# Arduino_Dots_Matrix.net
KiCad netlist of a schematic drawn in EAGLE
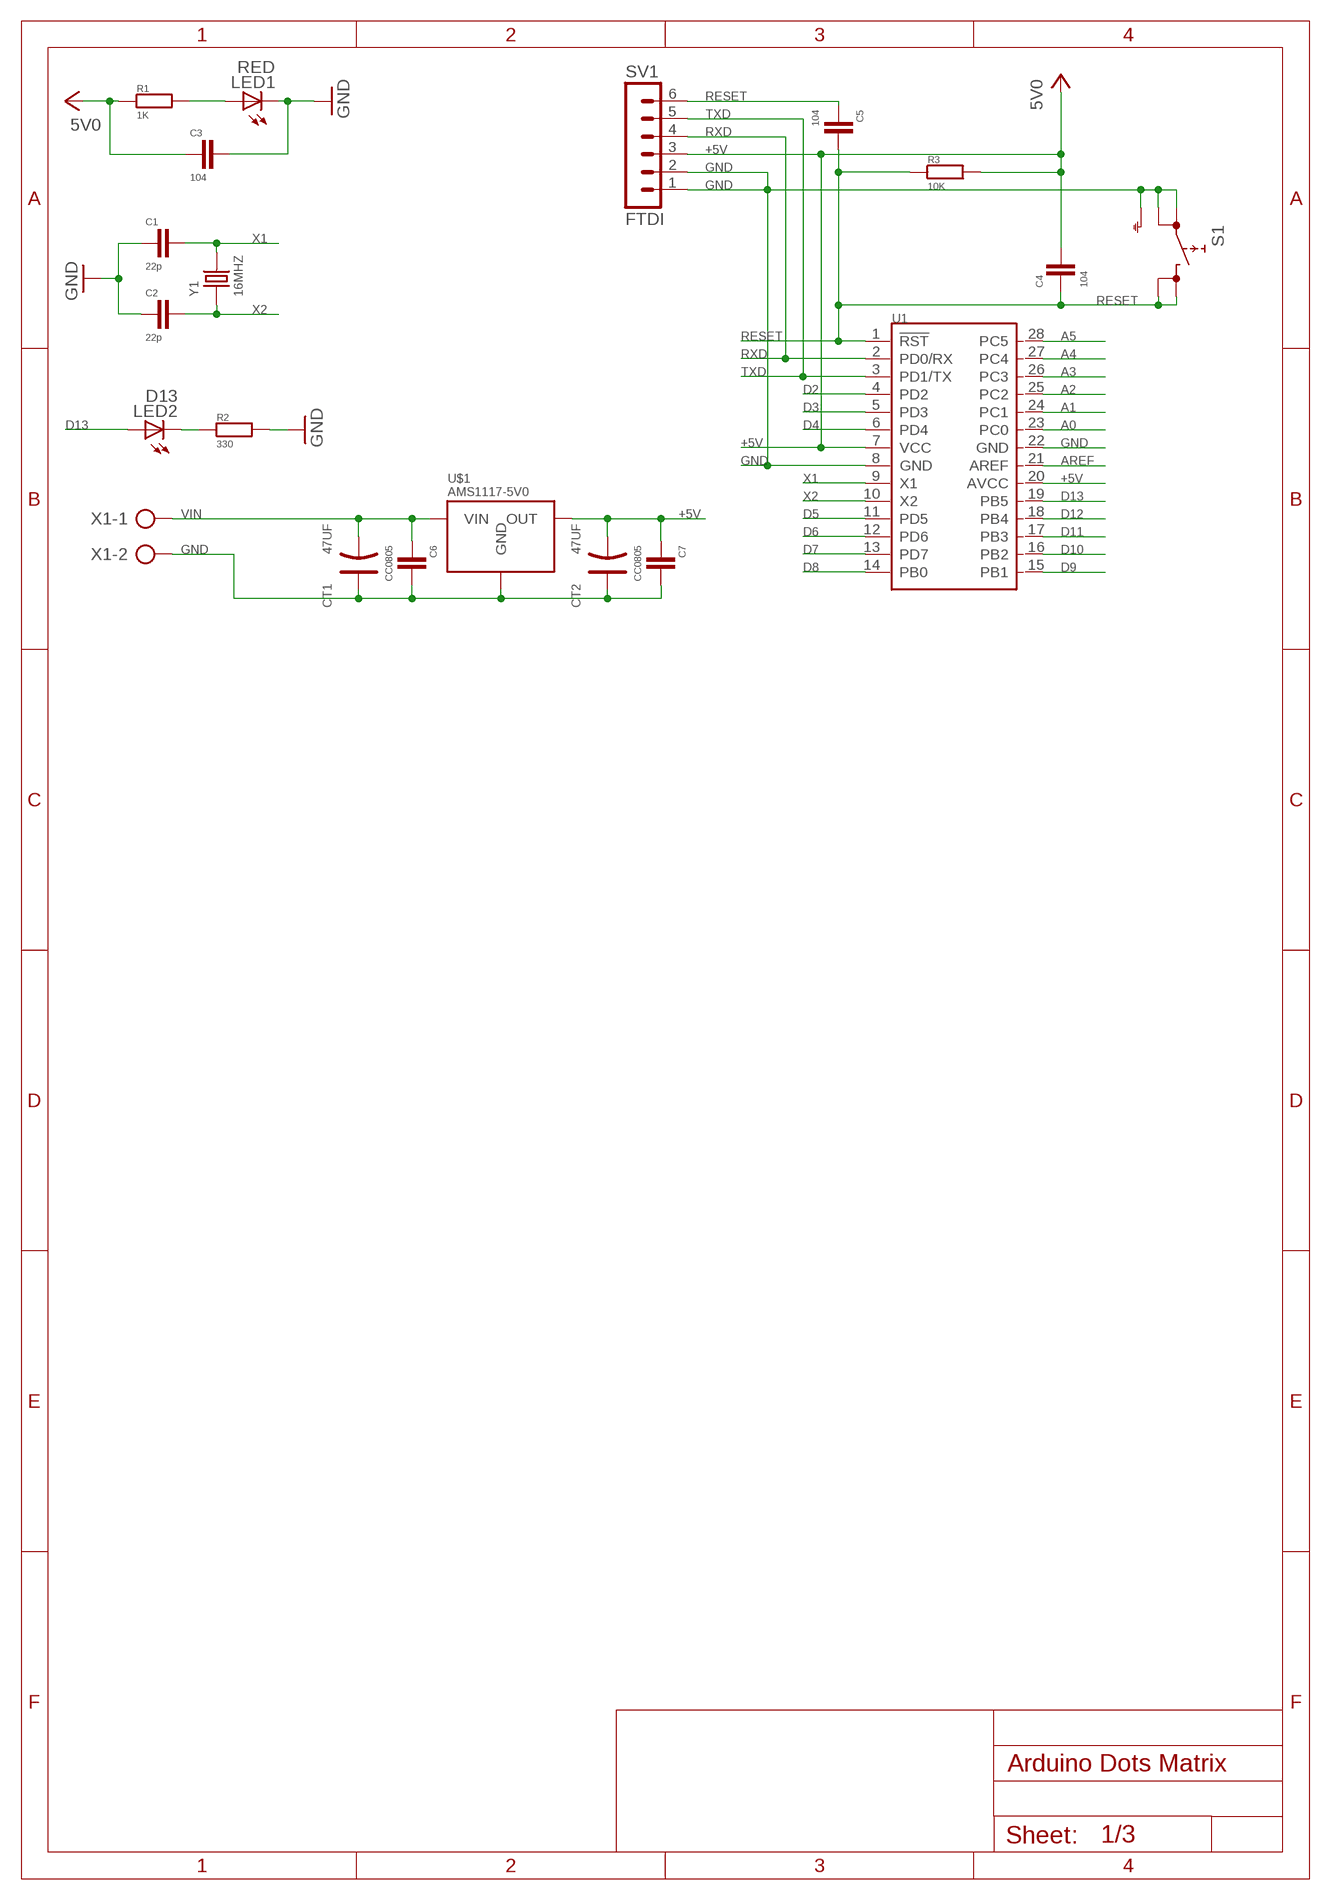
[diagram p0: schematic, sheet 1]
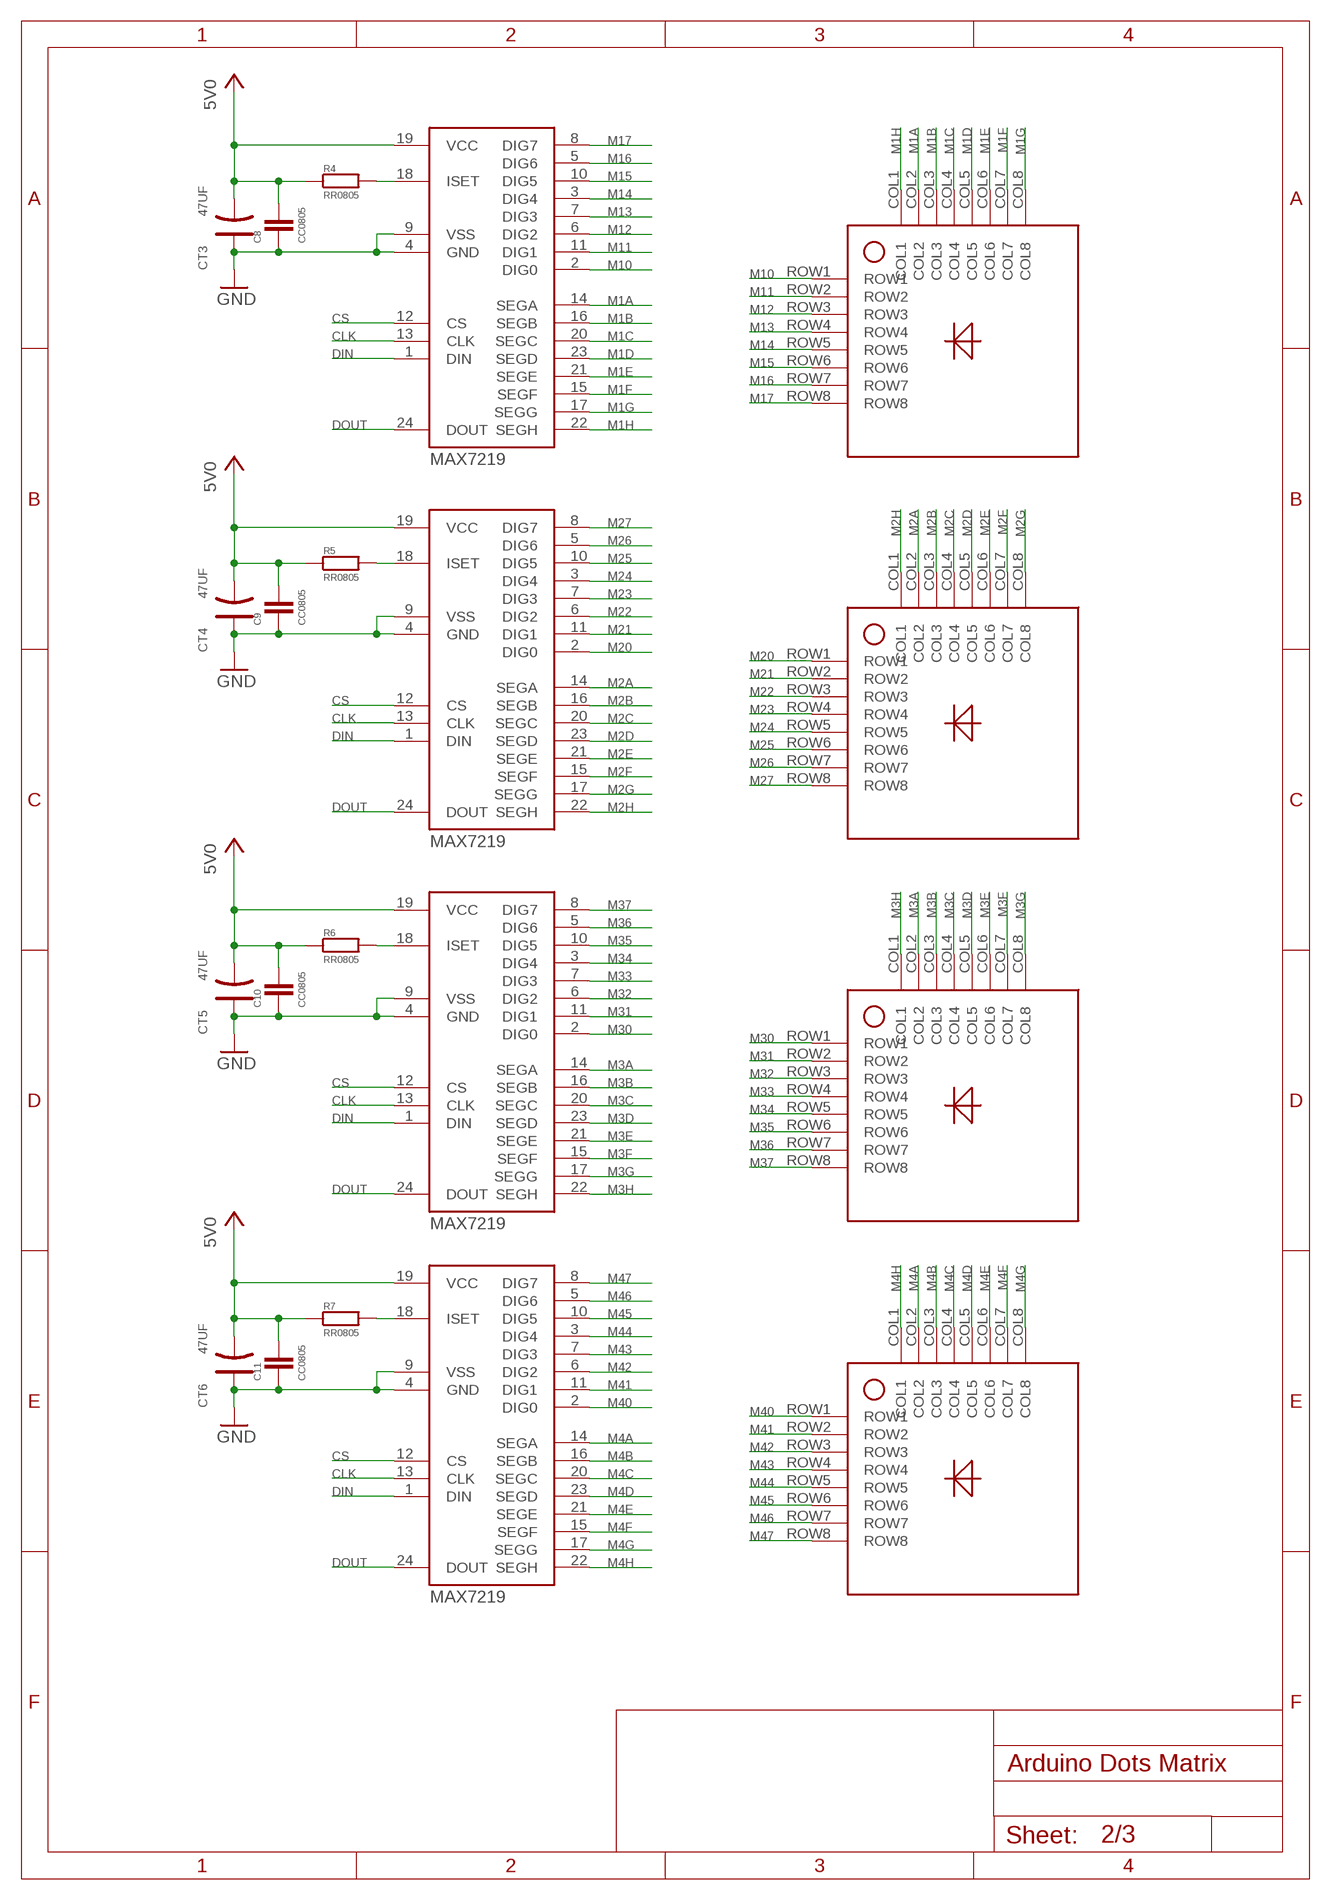
[diagram p1: schematic, sheet 2]
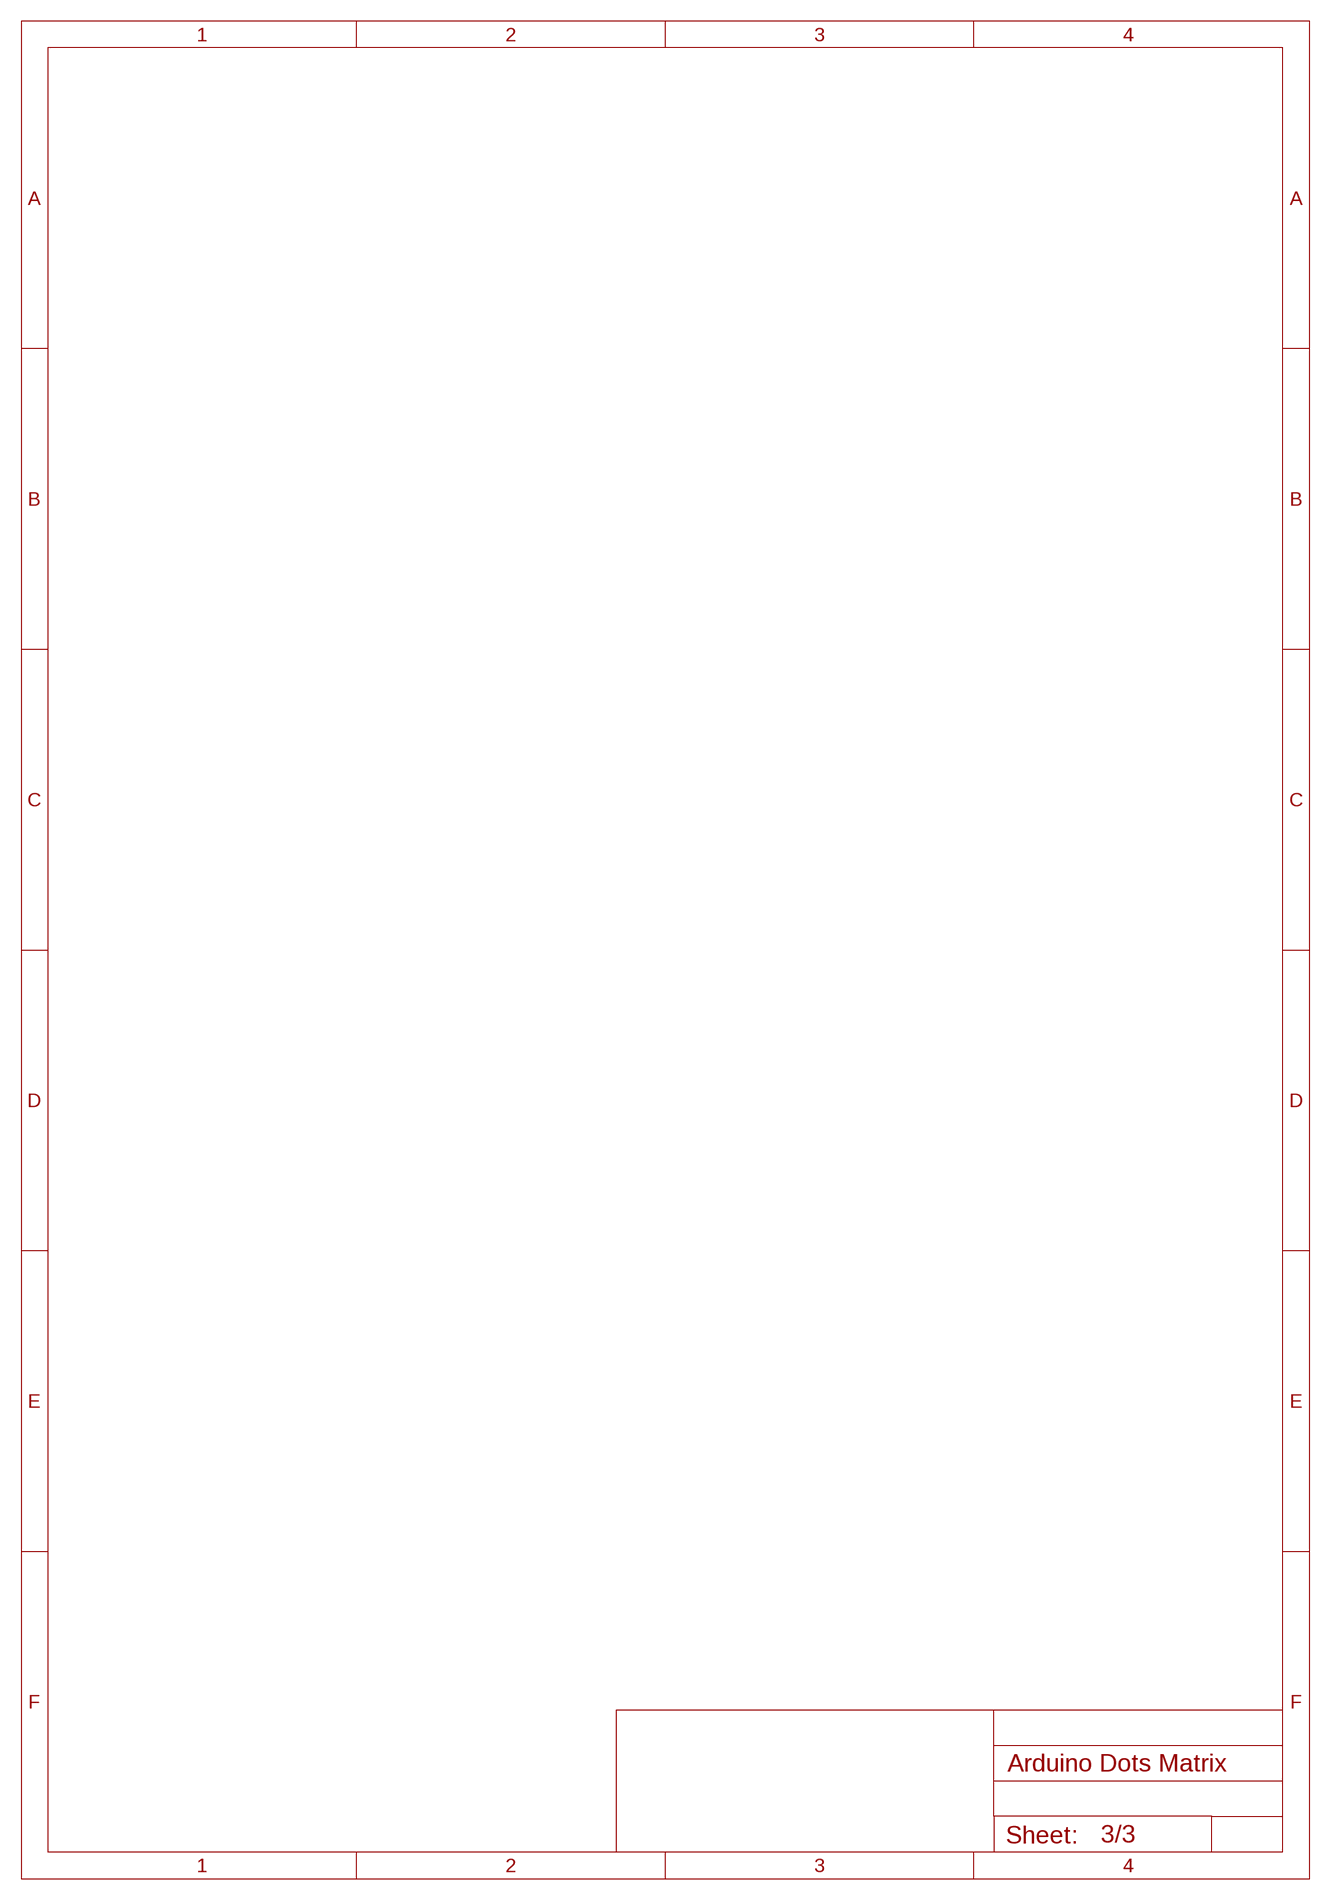
[diagram p2: schematic, sheet 3]

(export (version "E")
  (design (tool "Eeschema 10.0.6"))
  (components
    (comp (ref "C8")
      (value "CC0805")
      (footprint "eagle-import:C0805")
      (libsource (lib "eagle-import") (part "CC0805"))
    )
    (comp (ref "C9")
      (value "CC0805")
      (footprint "eagle-import:C0805")
      (libsource (lib "eagle-import") (part "CC0805"))
    )
    (comp (ref "C10")
      (value "CC0805")
      (footprint "eagle-import:C0805")
      (libsource (lib "eagle-import") (part "CC0805"))
    )
    (comp (ref "C11")
      (value "CC0805")
      (footprint "eagle-import:C0805")
      (libsource (lib "eagle-import") (part "CC0805"))
    )
    (comp (ref "CT3")
      (value "47UF")
      (footprint "eagle-import:ELECTRO-SMD-C-6MM")
      (fields (field (name "MPN") "CS1E470M-CRE54"))
      (libsource (lib "eagle-import") (part "ALUMINUM-SMD-47UF-25V(D6.3-H5.3MM)"))
    )
    (comp (ref "CT4")
      (value "47UF")
      (footprint "eagle-import:ELECTRO-SMD-C-6MM")
      (fields (field (name "MPN") "CS1E470M-CRE54"))
      (libsource (lib "eagle-import") (part "ALUMINUM-SMD-47UF-25V(D6.3-H5.3MM)"))
    )
    (comp (ref "CT5")
      (value "47UF")
      (footprint "eagle-import:ELECTRO-SMD-C-6MM")
      (fields (field (name "MPN") "CS1E470M-CRE54"))
      (libsource (lib "eagle-import") (part "ALUMINUM-SMD-47UF-25V(D6.3-H5.3MM)"))
    )
    (comp (ref "CT6")
      (value "47UF")
      (footprint "eagle-import:ELECTRO-SMD-C-6MM")
      (fields (field (name "MPN") "CS1E470M-CRE54"))
      (libsource (lib "eagle-import") (part "ALUMINUM-SMD-47UF-25V(D6.3-H5.3MM)"))
    )
    (comp (ref "D1")
      (value "DOT-MATRIX-AS")
      (footprint "eagle-import:1088AS")
      (libsource (lib "eagle-import") (part "DOT-MATRIX-AS"))
    )
    (comp (ref "D2")
      (value "DOT-MATRIX-AS")
      (footprint "eagle-import:1088AS")
      (libsource (lib "eagle-import") (part "DOT-MATRIX-AS"))
    )
    (comp (ref "D3")
      (value "DOT-MATRIX-AS")
      (footprint "eagle-import:1088AS")
      (libsource (lib "eagle-import") (part "DOT-MATRIX-AS"))
    )
    (comp (ref "D4")
      (value "DOT-MATRIX-AS")
      (footprint "eagle-import:1088AS")
      (libsource (lib "eagle-import") (part "DOT-MATRIX-AS"))
    )
    (comp (ref "M1")
      (value "MAX7219")
      (footprint "eagle-import:SOP24")
      (libsource (lib "eagle-import") (part "MAX7219"))
    )
    (comp (ref "M2")
      (value "MAX7219")
      (footprint "eagle-import:SOP24")
      (libsource (lib "eagle-import") (part "MAX7219"))
    )
    (comp (ref "M3")
      (value "MAX7219")
      (footprint "eagle-import:SOP24")
      (libsource (lib "eagle-import") (part "MAX7219"))
    )
    (comp (ref "M4")
      (value "MAX7219")
      (footprint "eagle-import:SOP24")
      (libsource (lib "eagle-import") (part "MAX7219"))
    )
    (comp (ref "R4")
      (value "RR0805")
      (footprint "eagle-import:R0805")
      (libsource (lib "eagle-import") (part "RR0805"))
    )
    (comp (ref "R5")
      (value "RR0805")
      (footprint "eagle-import:R0805")
      (libsource (lib "eagle-import") (part "RR0805"))
    )
    (comp (ref "R6")
      (value "RR0805")
      (footprint "eagle-import:R0805")
      (libsource (lib "eagle-import") (part "RR0805"))
    )
    (comp (ref "R7")
      (value "RR0805")
      (footprint "eagle-import:R0805")
      (libsource (lib "eagle-import") (part "RR0805"))
    )
    (comp (ref "C1")
      (value "22p")
      (footprint "eagle-import:C0805")
      (libsource (lib "eagle-import") (part "CC0805"))
    )
    (comp (ref "C2")
      (value "22p")
      (footprint "eagle-import:C0805")
      (libsource (lib "eagle-import") (part "CC0805"))
    )
    (comp (ref "C3")
      (value "104")
      (footprint "eagle-import:C0805")
      (libsource (lib "eagle-import") (part "CC0805"))
    )
    (comp (ref "C4")
      (value "104")
      (footprint "eagle-import:C0805")
      (libsource (lib "eagle-import") (part "CC0805"))
    )
    (comp (ref "C5")
      (value "104")
      (footprint "eagle-import:C0805")
      (libsource (lib "eagle-import") (part "CC0805"))
    )
    (comp (ref "C6")
      (value "CC0805")
      (footprint "eagle-import:C0805")
      (libsource (lib "eagle-import") (part "CC0805"))
    )
    (comp (ref "C7")
      (value "CC0805")
      (footprint "eagle-import:C0805")
      (libsource (lib "eagle-import") (part "CC0805"))
    )
    (comp (ref "CT1")
      (value "47UF")
      (footprint "eagle-import:ELECTRO-SMD-C-6MM")
      (fields (field (name "MPN") "CS1E470M-CRE54"))
      (libsource (lib "eagle-import") (part "ALUMINUM-SMD-47UF-25V(D6.3-H5.3MM)"))
    )
    (comp (ref "CT2")
      (value "47UF")
      (footprint "eagle-import:ELECTRO-SMD-C-6MM")
      (fields (field (name "MPN") "CS1E470M-CRE54"))
      (libsource (lib "eagle-import") (part "ALUMINUM-SMD-47UF-25V(D6.3-H5.3MM)"))
    )
    (comp (ref "LED1")
      (value "RED")
      (footprint "eagle-import:CHIPLED_0805")
      (libsource (lib "eagle-import") (part "LEDCHIPLED_0805"))
    )
    (comp (ref "LED2")
      (value "D13")
      (footprint "eagle-import:CHIPLED_0805")
      (libsource (lib "eagle-import") (part "LEDCHIPLED_0805"))
    )
    (comp (ref "R1")
      (value "1K")
      (footprint "eagle-import:R0805")
      (libsource (lib "eagle-import") (part "RR0805"))
    )
    (comp (ref "R2")
      (value "330")
      (footprint "eagle-import:R0805")
      (libsource (lib "eagle-import") (part "RR0805"))
    )
    (comp (ref "R3")
      (value "10K")
      (footprint "eagle-import:R0805")
      (libsource (lib "eagle-import") (part "RR0805"))
    )
    (comp (ref "S1")
      (value "SKHMPSE010")
      (footprint "eagle-import:SKHMPXE010")
      (libsource (lib "eagle-import") (part "SKHMPE010S"))
    )
    (comp (ref "SV1")
      (value "FTDI")
      (footprint "eagle-import:MA06-1")
      (libsource (lib "eagle-import") (part "MA06-1"))
    )
    (comp (ref "U$1")
      (value "AMS1117-5V0")
      (footprint "eagle-import:SOT223")
      (libsource (lib "eagle-import") (part "AMS1117-5V0SOT22"))
    )
    (comp (ref "U1")
      (value "MCU-ATMEGA328P-PU(DIP28)")
      (footprint "eagle-import:DIP28-2.54-35.6X13.5MM")
      (fields (field (name "MPN") "ATMEGA328P-PU"))
      (libsource (lib "eagle-import") (part "MCU-ATMEGA328P-PU(DIP28)"))
    )
    (comp (ref "X1")
      (value "AK500/2")
      (footprint "eagle-import:AK500_2")
      (libsource (lib "eagle-import") (part "AK500/2"))
    )
    (comp (ref "Y1")
      (value "16MHZ")
      (footprint "eagle-import:HC49US")
      (fields (field (name "MPN") "HC-49US    16.000MHz"))
      (libsource (lib "eagle-import") (part "DIP-CRYSTAL-16MHZ-18PF-30PPM-40R(HC49US)"))
    )
  )
  (nets
    (net (code "1") (name "+5V") (class "Default")
      (node (ref "C10") (pin "1") (pinfunction "1_1") (pintype "bidirectional"))
      (node (ref "C11") (pin "1") (pinfunction "1_1") (pintype "bidirectional"))
      (node (ref "C3") (pin "2") (pinfunction "2_2") (pintype "bidirectional"))
      (node (ref "C4") (pin "1") (pinfunction "1_1") (pintype "bidirectional"))
      (node (ref "C7") (pin "2") (pinfunction "2_2") (pintype "bidirectional"))
      (node (ref "C8") (pin "1") (pinfunction "1_1") (pintype "bidirectional"))
      (node (ref "C9") (pin "1") (pinfunction "1_1") (pintype "bidirectional"))
      (node (ref "CT2") (pin "-") (pinfunction "-_-") (pintype "passive"))
      (node (ref "CT3") (pin "-") (pinfunction "-_-") (pintype "passive"))
      (node (ref "CT4") (pin "-") (pinfunction "-_-") (pintype "passive"))
      (node (ref "CT5") (pin "-") (pinfunction "-_-") (pintype "passive"))
      (node (ref "CT6") (pin "-") (pinfunction "-_-") (pintype "passive"))
      (node (ref "M1") (pin "19") (pinfunction "VCC_19") (pintype "power_in"))
      (node (ref "M2") (pin "19") (pinfunction "VCC_19") (pintype "power_in"))
      (node (ref "M3") (pin "19") (pinfunction "VCC_19") (pintype "power_in"))
      (node (ref "M4") (pin "19") (pinfunction "VCC_19") (pintype "power_in"))
      (node (ref "R1") (pin "1") (pinfunction "1_1") (pintype "bidirectional"))
      (node (ref "R3") (pin "2") (pinfunction "2_2") (pintype "bidirectional"))
      (node (ref "R4") (pin "1") (pinfunction "1_1") (pintype "bidirectional"))
      (node (ref "R5") (pin "1") (pinfunction "1_1") (pintype "bidirectional"))
      (node (ref "R6") (pin "1") (pinfunction "1_1") (pintype "bidirectional"))
      (node (ref "R7") (pin "1") (pinfunction "1_1") (pintype "bidirectional"))
      (node (ref "SV1") (pin "3") (pinfunction "3_3") (pintype "passive"))
      (node (ref "U$1") (pin "OUT") (pinfunction "OUT_OUT") (pintype "bidirectional"))
      (node (ref "U1") (pin "20") (pinfunction "AVCC_20") (pintype "bidirectional"))
      (node (ref "U1") (pin "7") (pinfunction "VCC_7") (pintype "bidirectional"))
    )
    (net (code "2") (name "A0") (class "Default")
      (node (ref "U1") (pin "23") (pinfunction "PC0_23") (pintype "bidirectional"))
    )
    (net (code "3") (name "A1") (class "Default")
      (node (ref "U1") (pin "24") (pinfunction "PC1_24") (pintype "bidirectional"))
    )
    (net (code "4") (name "A2") (class "Default")
      (node (ref "U1") (pin "25") (pinfunction "PC2_25") (pintype "bidirectional"))
    )
    (net (code "5") (name "A3") (class "Default")
      (node (ref "U1") (pin "26") (pinfunction "PC3_26") (pintype "bidirectional"))
    )
    (net (code "6") (name "A4") (class "Default")
      (node (ref "U1") (pin "27") (pinfunction "PC4_27") (pintype "bidirectional"))
    )
    (net (code "7") (name "A5") (class "Default")
      (node (ref "U1") (pin "28") (pinfunction "PC5_28") (pintype "bidirectional"))
    )
    (net (code "8") (name "AREF") (class "Default")
      (node (ref "U1") (pin "21") (pinfunction "AREF_21") (pintype "bidirectional"))
    )
    (net (code "9") (name "CLK") (class "Default")
      (node (ref "M1") (pin "13") (pinfunction "CLK_13") (pintype "input"))
      (node (ref "M2") (pin "13") (pinfunction "CLK_13") (pintype "input"))
      (node (ref "M3") (pin "13") (pinfunction "CLK_13") (pintype "input"))
      (node (ref "M4") (pin "13") (pinfunction "CLK_13") (pintype "input"))
    )
    (net (code "10") (name "CS") (class "Default")
      (node (ref "M1") (pin "12") (pinfunction "CS_12") (pintype "input"))
      (node (ref "M2") (pin "12") (pinfunction "CS_12") (pintype "input"))
      (node (ref "M3") (pin "12") (pinfunction "CS_12") (pintype "input"))
      (node (ref "M4") (pin "12") (pinfunction "CS_12") (pintype "input"))
    )
    (net (code "11") (name "D2") (class "Default")
      (node (ref "U1") (pin "4") (pinfunction "PD2_4") (pintype "bidirectional"))
    )
    (net (code "12") (name "D3") (class "Default")
      (node (ref "U1") (pin "5") (pinfunction "PD3_5") (pintype "bidirectional"))
    )
    (net (code "13") (name "D4") (class "Default")
      (node (ref "U1") (pin "6") (pinfunction "PD4_6") (pintype "bidirectional"))
    )
    (net (code "14") (name "D5") (class "Default")
      (node (ref "U1") (pin "11") (pinfunction "PD5_11") (pintype "bidirectional"))
    )
    (net (code "15") (name "D6") (class "Default")
      (node (ref "U1") (pin "12") (pinfunction "PD6_12") (pintype "bidirectional"))
    )
    (net (code "16") (name "D7") (class "Default")
      (node (ref "U1") (pin "13") (pinfunction "PD7_13") (pintype "bidirectional"))
    )
    (net (code "17") (name "D8") (class "Default")
      (node (ref "U1") (pin "14") (pinfunction "PB0_14") (pintype "bidirectional"))
    )
    (net (code "18") (name "D9") (class "Default")
      (node (ref "U1") (pin "15") (pinfunction "PB1_15") (pintype "bidirectional"))
    )
    (net (code "19") (name "D10") (class "Default")
      (node (ref "U1") (pin "16") (pinfunction "PB2_16") (pintype "bidirectional"))
    )
    (net (code "20") (name "D11") (class "Default")
      (node (ref "U1") (pin "17") (pinfunction "PB3_17") (pintype "bidirectional"))
    )
    (net (code "21") (name "D12") (class "Default")
      (node (ref "U1") (pin "18") (pinfunction "PB4_18") (pintype "bidirectional"))
    )
    (net (code "22") (name "D13") (class "Default")
      (node (ref "LED2") (pin "A") (pinfunction "A_A") (pintype "passive"))
      (node (ref "U1") (pin "19") (pinfunction "PB5_19") (pintype "bidirectional"))
    )
    (net (code "23") (name "DIN") (class "Default")
      (node (ref "M1") (pin "1") (pinfunction "DIN_1") (pintype "input"))
      (node (ref "M2") (pin "1") (pinfunction "DIN_1") (pintype "input"))
      (node (ref "M3") (pin "1") (pinfunction "DIN_1") (pintype "input"))
      (node (ref "M4") (pin "1") (pinfunction "DIN_1") (pintype "input"))
    )
    (net (code "24") (name "DOUT") (class "Default")
      (node (ref "M1") (pin "24") (pinfunction "DOUT_24") (pintype "input"))
      (node (ref "M2") (pin "24") (pinfunction "DOUT_24") (pintype "input"))
      (node (ref "M3") (pin "24") (pinfunction "DOUT_24") (pintype "input"))
      (node (ref "M4") (pin "24") (pinfunction "DOUT_24") (pintype "input"))
    )
    (net (code "25") (name "GND") (class "Default")
      (node (ref "C1") (pin "2") (pinfunction "2_2") (pintype "bidirectional"))
      (node (ref "C10") (pin "2") (pinfunction "2_2") (pintype "bidirectional"))
      (node (ref "C11") (pin "2") (pinfunction "2_2") (pintype "bidirectional"))
      (node (ref "C2") (pin "2") (pinfunction "2_2") (pintype "bidirectional"))
      (node (ref "C3") (pin "1") (pinfunction "1_1") (pintype "bidirectional"))
      (node (ref "C6") (pin "1") (pinfunction "1_1") (pintype "bidirectional"))
      (node (ref "C7") (pin "1") (pinfunction "1_1") (pintype "bidirectional"))
      (node (ref "C8") (pin "2") (pinfunction "2_2") (pintype "bidirectional"))
      (node (ref "C9") (pin "2") (pinfunction "2_2") (pintype "bidirectional"))
      (node (ref "CT1") (pin "+") (pinfunction "+_+") (pintype "passive"))
      (node (ref "CT2") (pin "+") (pinfunction "+_+") (pintype "passive"))
      (node (ref "CT3") (pin "+") (pinfunction "+_+") (pintype "passive"))
      (node (ref "CT4") (pin "+") (pinfunction "+_+") (pintype "passive"))
      (node (ref "CT5") (pin "+") (pinfunction "+_+") (pintype "passive"))
      (node (ref "CT6") (pin "+") (pinfunction "+_+") (pintype "passive"))
      (node (ref "LED1") (pin "C") (pinfunction "C_C") (pintype "passive"))
      (node (ref "M1") (pin "4") (pinfunction "GND_4") (pintype "power_in"))
      (node (ref "M1") (pin "9") (pinfunction "VSS_9") (pintype "power_in"))
      (node (ref "M2") (pin "4") (pinfunction "GND_4") (pintype "power_in"))
      (node (ref "M2") (pin "9") (pinfunction "VSS_9") (pintype "power_in"))
      (node (ref "M3") (pin "4") (pinfunction "GND_4") (pintype "power_in"))
      (node (ref "M3") (pin "9") (pinfunction "VSS_9") (pintype "power_in"))
      (node (ref "M4") (pin "4") (pinfunction "GND_4") (pintype "power_in"))
      (node (ref "M4") (pin "9") (pinfunction "VSS_9") (pintype "power_in"))
      (node (ref "R2") (pin "2") (pinfunction "2_2") (pintype "bidirectional"))
      (node (ref "S1") (pin "1") (pinfunction "1.1_1") (pintype "passive"))
      (node (ref "S1") (pin "2") (pinfunction "1.2_2") (pintype "passive"))
      (node (ref "S1") (pin "5") (pinfunction "SH_5") (pintype "passive"))
      (node (ref "SV1") (pin "1") (pinfunction "1_1") (pintype "passive"))
      (node (ref "SV1") (pin "2") (pinfunction "2_2") (pintype "passive"))
      (node (ref "U$1") (pin "GND") (pinfunction "GND_GND") (pintype "bidirectional"))
      (node (ref "U1") (pin "22") (pinfunction "GND_22") (pintype "bidirectional"))
      (node (ref "U1") (pin "8") (pinfunction "GND_8") (pintype "bidirectional"))
      (node (ref "X1") (pin "2") (pinfunction "KL_2") (pintype "passive"))
    )
    (net (code "26") (name "M1A") (class "Default")
      (node (ref "D1") (pin "COL2") (pinfunction "COL2_COL2") (pintype "bidirectional"))
      (node (ref "M1") (pin "14") (pinfunction "SEGA_14") (pintype "input"))
    )
    (net (code "27") (name "M1B") (class "Default")
      (node (ref "D1") (pin "COL3") (pinfunction "COL3_COL3") (pintype "bidirectional"))
      (node (ref "M1") (pin "16") (pinfunction "SEGB_16") (pintype "input"))
    )
    (net (code "28") (name "M1C") (class "Default")
      (node (ref "D1") (pin "COL4") (pinfunction "COL4_COL4") (pintype "bidirectional"))
      (node (ref "M1") (pin "20") (pinfunction "SEGC_20") (pintype "input"))
    )
    (net (code "29") (name "M1D") (class "Default")
      (node (ref "D1") (pin "COL5") (pinfunction "COL5_COL5") (pintype "bidirectional"))
      (node (ref "M1") (pin "23") (pinfunction "SEGD_23") (pintype "input"))
    )
    (net (code "30") (name "M1E") (class "Default")
      (node (ref "D1") (pin "COL6") (pinfunction "COL6_COL6") (pintype "bidirectional"))
      (node (ref "M1") (pin "21") (pinfunction "SEGE_21") (pintype "input"))
    )
    (net (code "31") (name "M1F") (class "Default")
      (node (ref "D1") (pin "COL7") (pinfunction "COL7_COL7") (pintype "bidirectional"))
      (node (ref "M1") (pin "15") (pinfunction "SEGF_15") (pintype "input"))
    )
    (net (code "32") (name "M1G") (class "Default")
      (node (ref "D1") (pin "COL8") (pinfunction "COL8_COL8") (pintype "bidirectional"))
      (node (ref "M1") (pin "17") (pinfunction "SEGG_17") (pintype "input"))
    )
    (net (code "33") (name "M1H") (class "Default")
      (node (ref "D1") (pin "COL1") (pinfunction "COL1_COL1") (pintype "bidirectional"))
      (node (ref "M1") (pin "22") (pinfunction "SEGH_22") (pintype "input"))
    )
    (net (code "34") (name "M2A") (class "Default")
      (node (ref "D2") (pin "COL2") (pinfunction "COL2_COL2") (pintype "bidirectional"))
      (node (ref "M2") (pin "14") (pinfunction "SEGA_14") (pintype "input"))
    )
    (net (code "35") (name "M2B") (class "Default")
      (node (ref "D2") (pin "COL3") (pinfunction "COL3_COL3") (pintype "bidirectional"))
      (node (ref "M2") (pin "16") (pinfunction "SEGB_16") (pintype "input"))
    )
    (net (code "36") (name "M2C") (class "Default")
      (node (ref "D2") (pin "COL4") (pinfunction "COL4_COL4") (pintype "bidirectional"))
      (node (ref "M2") (pin "20") (pinfunction "SEGC_20") (pintype "input"))
    )
    (net (code "37") (name "M2D") (class "Default")
      (node (ref "D2") (pin "COL5") (pinfunction "COL5_COL5") (pintype "bidirectional"))
      (node (ref "M2") (pin "23") (pinfunction "SEGD_23") (pintype "input"))
    )
    (net (code "38") (name "M2E") (class "Default")
      (node (ref "D2") (pin "COL6") (pinfunction "COL6_COL6") (pintype "bidirectional"))
      (node (ref "M2") (pin "21") (pinfunction "SEGE_21") (pintype "input"))
    )
    (net (code "39") (name "M2F") (class "Default")
      (node (ref "D2") (pin "COL7") (pinfunction "COL7_COL7") (pintype "bidirectional"))
      (node (ref "M2") (pin "15") (pinfunction "SEGF_15") (pintype "input"))
    )
    (net (code "40") (name "M2G") (class "Default")
      (node (ref "D2") (pin "COL8") (pinfunction "COL8_COL8") (pintype "bidirectional"))
      (node (ref "M2") (pin "17") (pinfunction "SEGG_17") (pintype "input"))
    )
    (net (code "41") (name "M2H") (class "Default")
      (node (ref "D2") (pin "COL1") (pinfunction "COL1_COL1") (pintype "bidirectional"))
      (node (ref "M2") (pin "22") (pinfunction "SEGH_22") (pintype "input"))
    )
    (net (code "42") (name "M3A") (class "Default")
      (node (ref "D3") (pin "COL2") (pinfunction "COL2_COL2") (pintype "bidirectional"))
      (node (ref "M3") (pin "14") (pinfunction "SEGA_14") (pintype "input"))
    )
    (net (code "43") (name "M3B") (class "Default")
      (node (ref "D3") (pin "COL3") (pinfunction "COL3_COL3") (pintype "bidirectional"))
      (node (ref "M3") (pin "16") (pinfunction "SEGB_16") (pintype "input"))
    )
    (net (code "44") (name "M3C") (class "Default")
      (node (ref "D3") (pin "COL4") (pinfunction "COL4_COL4") (pintype "bidirectional"))
      (node (ref "M3") (pin "20") (pinfunction "SEGC_20") (pintype "input"))
    )
    (net (code "45") (name "M3D") (class "Default")
      (node (ref "D3") (pin "COL5") (pinfunction "COL5_COL5") (pintype "bidirectional"))
      (node (ref "M3") (pin "23") (pinfunction "SEGD_23") (pintype "input"))
    )
    (net (code "46") (name "M3E") (class "Default")
      (node (ref "D3") (pin "COL6") (pinfunction "COL6_COL6") (pintype "bidirectional"))
      (node (ref "M3") (pin "21") (pinfunction "SEGE_21") (pintype "input"))
    )
    (net (code "47") (name "M3F") (class "Default")
      (node (ref "D3") (pin "COL7") (pinfunction "COL7_COL7") (pintype "bidirectional"))
      (node (ref "M3") (pin "15") (pinfunction "SEGF_15") (pintype "input"))
    )
    (net (code "48") (name "M3G") (class "Default")
      (node (ref "D3") (pin "COL8") (pinfunction "COL8_COL8") (pintype "bidirectional"))
      (node (ref "M3") (pin "17") (pinfunction "SEGG_17") (pintype "input"))
    )
    (net (code "49") (name "M3H") (class "Default")
      (node (ref "D3") (pin "COL1") (pinfunction "COL1_COL1") (pintype "bidirectional"))
      (node (ref "M3") (pin "22") (pinfunction "SEGH_22") (pintype "input"))
    )
    (net (code "50") (name "M4A") (class "Default")
      (node (ref "D4") (pin "COL2") (pinfunction "COL2_COL2") (pintype "bidirectional"))
      (node (ref "M4") (pin "14") (pinfunction "SEGA_14") (pintype "input"))
    )
    (net (code "51") (name "M4B") (class "Default")
      (node (ref "D4") (pin "COL3") (pinfunction "COL3_COL3") (pintype "bidirectional"))
      (node (ref "M4") (pin "16") (pinfunction "SEGB_16") (pintype "input"))
    )
    (net (code "52") (name "M4C") (class "Default")
      (node (ref "D4") (pin "COL4") (pinfunction "COL4_COL4") (pintype "bidirectional"))
      (node (ref "M4") (pin "20") (pinfunction "SEGC_20") (pintype "input"))
    )
    (net (code "53") (name "M4D") (class "Default")
      (node (ref "D4") (pin "COL5") (pinfunction "COL5_COL5") (pintype "bidirectional"))
      (node (ref "M4") (pin "23") (pinfunction "SEGD_23") (pintype "input"))
    )
    (net (code "54") (name "M4E") (class "Default")
      (node (ref "D4") (pin "COL6") (pinfunction "COL6_COL6") (pintype "bidirectional"))
      (node (ref "M4") (pin "21") (pinfunction "SEGE_21") (pintype "input"))
    )
    (net (code "55") (name "M4F") (class "Default")
      (node (ref "D4") (pin "COL7") (pinfunction "COL7_COL7") (pintype "bidirectional"))
      (node (ref "M4") (pin "15") (pinfunction "SEGF_15") (pintype "input"))
    )
    (net (code "56") (name "M4G") (class "Default")
      (node (ref "D4") (pin "COL8") (pinfunction "COL8_COL8") (pintype "bidirectional"))
      (node (ref "M4") (pin "17") (pinfunction "SEGG_17") (pintype "input"))
    )
    (net (code "57") (name "M4H") (class "Default")
      (node (ref "D4") (pin "COL1") (pinfunction "COL1_COL1") (pintype "bidirectional"))
      (node (ref "M4") (pin "22") (pinfunction "SEGH_22") (pintype "input"))
    )
    (net (code "58") (name "M10") (class "Default")
      (node (ref "D1") (pin "ROW1") (pinfunction "ROW1_ROW1") (pintype "bidirectional"))
      (node (ref "M1") (pin "2") (pinfunction "DIG0_2") (pintype "input"))
    )
    (net (code "59") (name "M11") (class "Default")
      (node (ref "D1") (pin "ROW2") (pinfunction "ROW2_ROW2") (pintype "bidirectional"))
      (node (ref "M1") (pin "11") (pinfunction "DIG1_11") (pintype "input"))
    )
    (net (code "60") (name "M12") (class "Default")
      (node (ref "D1") (pin "ROW3") (pinfunction "ROW3_ROW3") (pintype "bidirectional"))
      (node (ref "M1") (pin "6") (pinfunction "DIG2_6") (pintype "input"))
    )
    (net (code "61") (name "M13") (class "Default")
      (node (ref "D1") (pin "ROW4") (pinfunction "ROW4_ROW4") (pintype "bidirectional"))
      (node (ref "M1") (pin "7") (pinfunction "DIG3_7") (pintype "input"))
    )
    (net (code "62") (name "M14") (class "Default")
      (node (ref "D1") (pin "ROW5") (pinfunction "ROW5_ROW5") (pintype "bidirectional"))
      (node (ref "M1") (pin "3") (pinfunction "DIG4_3") (pintype "input"))
    )
    (net (code "63") (name "M15") (class "Default")
      (node (ref "D1") (pin "ROW6") (pinfunction "ROW6_ROW6") (pintype "bidirectional"))
      (node (ref "M1") (pin "10") (pinfunction "DIG5_10") (pintype "input"))
    )
    (net (code "64") (name "M16") (class "Default")
      (node (ref "D1") (pin "ROW7") (pinfunction "ROW7_ROW7") (pintype "bidirectional"))
      (node (ref "M1") (pin "5") (pinfunction "DIG6_5") (pintype "input"))
    )
    (net (code "65") (name "M17") (class "Default")
      (node (ref "D1") (pin "ROW8") (pinfunction "ROW8_ROW8") (pintype "bidirectional"))
      (node (ref "M1") (pin "8") (pinfunction "DIG7_8") (pintype "input"))
    )
    (net (code "66") (name "M20") (class "Default")
      (node (ref "D2") (pin "ROW1") (pinfunction "ROW1_ROW1") (pintype "bidirectional"))
      (node (ref "M2") (pin "2") (pinfunction "DIG0_2") (pintype "input"))
    )
    (net (code "67") (name "M21") (class "Default")
      (node (ref "D2") (pin "ROW2") (pinfunction "ROW2_ROW2") (pintype "bidirectional"))
      (node (ref "M2") (pin "11") (pinfunction "DIG1_11") (pintype "input"))
    )
    (net (code "68") (name "M22") (class "Default")
      (node (ref "D2") (pin "ROW3") (pinfunction "ROW3_ROW3") (pintype "bidirectional"))
      (node (ref "M2") (pin "6") (pinfunction "DIG2_6") (pintype "input"))
    )
    (net (code "69") (name "M23") (class "Default")
      (node (ref "D2") (pin "ROW4") (pinfunction "ROW4_ROW4") (pintype "bidirectional"))
      (node (ref "M2") (pin "7") (pinfunction "DIG3_7") (pintype "input"))
    )
    (net (code "70") (name "M24") (class "Default")
      (node (ref "D2") (pin "ROW5") (pinfunction "ROW5_ROW5") (pintype "bidirectional"))
      (node (ref "M2") (pin "3") (pinfunction "DIG4_3") (pintype "input"))
    )
    (net (code "71") (name "M25") (class "Default")
      (node (ref "D2") (pin "ROW6") (pinfunction "ROW6_ROW6") (pintype "bidirectional"))
      (node (ref "M2") (pin "10") (pinfunction "DIG5_10") (pintype "input"))
    )
    (net (code "72") (name "M26") (class "Default")
      (node (ref "D2") (pin "ROW7") (pinfunction "ROW7_ROW7") (pintype "bidirectional"))
      (node (ref "M2") (pin "5") (pinfunction "DIG6_5") (pintype "input"))
    )
    (net (code "73") (name "M27") (class "Default")
      (node (ref "D2") (pin "ROW8") (pinfunction "ROW8_ROW8") (pintype "bidirectional"))
      (node (ref "M2") (pin "8") (pinfunction "DIG7_8") (pintype "input"))
    )
    (net (code "74") (name "M30") (class "Default")
      (node (ref "D3") (pin "ROW1") (pinfunction "ROW1_ROW1") (pintype "bidirectional"))
      (node (ref "M3") (pin "2") (pinfunction "DIG0_2") (pintype "input"))
    )
    (net (code "75") (name "M31") (class "Default")
      (node (ref "D3") (pin "ROW2") (pinfunction "ROW2_ROW2") (pintype "bidirectional"))
      (node (ref "M3") (pin "11") (pinfunction "DIG1_11") (pintype "input"))
    )
    (net (code "76") (name "M32") (class "Default")
      (node (ref "D3") (pin "ROW3") (pinfunction "ROW3_ROW3") (pintype "bidirectional"))
      (node (ref "M3") (pin "6") (pinfunction "DIG2_6") (pintype "input"))
    )
    (net (code "77") (name "M33") (class "Default")
      (node (ref "D3") (pin "ROW4") (pinfunction "ROW4_ROW4") (pintype "bidirectional"))
      (node (ref "M3") (pin "7") (pinfunction "DIG3_7") (pintype "input"))
    )
    (net (code "78") (name "M34") (class "Default")
      (node (ref "D3") (pin "ROW5") (pinfunction "ROW5_ROW5") (pintype "bidirectional"))
      (node (ref "M3") (pin "3") (pinfunction "DIG4_3") (pintype "input"))
    )
    (net (code "79") (name "M35") (class "Default")
      (node (ref "D3") (pin "ROW6") (pinfunction "ROW6_ROW6") (pintype "bidirectional"))
      (node (ref "M3") (pin "10") (pinfunction "DIG5_10") (pintype "input"))
    )
    (net (code "80") (name "M36") (class "Default")
      (node (ref "D3") (pin "ROW7") (pinfunction "ROW7_ROW7") (pintype "bidirectional"))
      (node (ref "M3") (pin "5") (pinfunction "DIG6_5") (pintype "input"))
    )
    (net (code "81") (name "M37") (class "Default")
      (node (ref "D3") (pin "ROW8") (pinfunction "ROW8_ROW8") (pintype "bidirectional"))
      (node (ref "M3") (pin "8") (pinfunction "DIG7_8") (pintype "input"))
    )
    (net (code "82") (name "M40") (class "Default")
      (node (ref "D4") (pin "ROW1") (pinfunction "ROW1_ROW1") (pintype "bidirectional"))
      (node (ref "M4") (pin "2") (pinfunction "DIG0_2") (pintype "input"))
    )
    (net (code "83") (name "M41") (class "Default")
      (node (ref "D4") (pin "ROW2") (pinfunction "ROW2_ROW2") (pintype "bidirectional"))
      (node (ref "M4") (pin "11") (pinfunction "DIG1_11") (pintype "input"))
    )
    (net (code "84") (name "M42") (class "Default")
      (node (ref "D4") (pin "ROW3") (pinfunction "ROW3_ROW3") (pintype "bidirectional"))
      (node (ref "M4") (pin "6") (pinfunction "DIG2_6") (pintype "input"))
    )
    (net (code "85") (name "M43") (class "Default")
      (node (ref "D4") (pin "ROW4") (pinfunction "ROW4_ROW4") (pintype "bidirectional"))
      (node (ref "M4") (pin "7") (pinfunction "DIG3_7") (pintype "input"))
    )
    (net (code "86") (name "M44") (class "Default")
      (node (ref "D4") (pin "ROW5") (pinfunction "ROW5_ROW5") (pintype "bidirectional"))
      (node (ref "M4") (pin "3") (pinfunction "DIG4_3") (pintype "input"))
    )
    (net (code "87") (name "M45") (class "Default")
      (node (ref "D4") (pin "ROW6") (pinfunction "ROW6_ROW6") (pintype "bidirectional"))
      (node (ref "M4") (pin "10") (pinfunction "DIG5_10") (pintype "input"))
    )
    (net (code "88") (name "M46") (class "Default")
      (node (ref "D4") (pin "ROW7") (pinfunction "ROW7_ROW7") (pintype "bidirectional"))
      (node (ref "M4") (pin "5") (pinfunction "DIG6_5") (pintype "input"))
    )
    (net (code "89") (name "M47") (class "Default")
      (node (ref "D4") (pin "ROW8") (pinfunction "ROW8_ROW8") (pintype "bidirectional"))
      (node (ref "M4") (pin "8") (pinfunction "DIG7_8") (pintype "input"))
    )
    (net (code "90") (name "Net-(LED1-PadA)") (class "Default")
      (node (ref "LED1") (pin "A") (pinfunction "A_A") (pintype "passive"))
      (node (ref "R1") (pin "2") (pinfunction "2_2") (pintype "bidirectional"))
    )
    (net (code "91") (name "Net-(LED2-PadC)") (class "Default")
      (node (ref "LED2") (pin "C") (pinfunction "C_C") (pintype "passive"))
      (node (ref "R2") (pin "1") (pinfunction "1_1") (pintype "bidirectional"))
    )
    (net (code "92") (name "Net-(M1-ISET)") (class "Default")
      (node (ref "M1") (pin "18") (pinfunction "ISET_18") (pintype "input"))
      (node (ref "R4") (pin "2") (pinfunction "2_2") (pintype "bidirectional"))
    )
    (net (code "93") (name "Net-(M2-ISET)") (class "Default")
      (node (ref "M2") (pin "18") (pinfunction "ISET_18") (pintype "input"))
      (node (ref "R5") (pin "2") (pinfunction "2_2") (pintype "bidirectional"))
    )
    (net (code "94") (name "Net-(M3-ISET)") (class "Default")
      (node (ref "M3") (pin "18") (pinfunction "ISET_18") (pintype "input"))
      (node (ref "R6") (pin "2") (pinfunction "2_2") (pintype "bidirectional"))
    )
    (net (code "95") (name "Net-(M4-ISET)") (class "Default")
      (node (ref "M4") (pin "18") (pinfunction "ISET_18") (pintype "input"))
      (node (ref "R7") (pin "2") (pinfunction "2_2") (pintype "bidirectional"))
    )
    (net (code "96") (name "RESET") (class "Default")
      (node (ref "C4") (pin "2") (pinfunction "2_2") (pintype "bidirectional"))
      (node (ref "C5") (pin "1") (pinfunction "1_1") (pintype "bidirectional"))
      (node (ref "C5") (pin "2") (pinfunction "2_2") (pintype "bidirectional"))
      (node (ref "R3") (pin "1") (pinfunction "1_1") (pintype "bidirectional"))
      (node (ref "S1") (pin "3") (pinfunction "2.1_3") (pintype "passive"))
      (node (ref "S1") (pin "4") (pinfunction "2.2_4") (pintype "passive"))
      (node (ref "SV1") (pin "6") (pinfunction "6_6") (pintype "passive"))
      (node (ref "U1") (pin "1") (pinfunction "~{RST}_1") (pintype "bidirectional"))
    )
    (net (code "97") (name "RXD") (class "Default")
      (node (ref "SV1") (pin "4") (pinfunction "4_4") (pintype "passive"))
      (node (ref "U1") (pin "2") (pinfunction "PD0/RX_2") (pintype "bidirectional"))
    )
    (net (code "98") (name "TXD") (class "Default")
      (node (ref "SV1") (pin "5") (pinfunction "5_5") (pintype "passive"))
      (node (ref "U1") (pin "3") (pinfunction "PD1/TX_3") (pintype "bidirectional"))
    )
    (net (code "99") (name "VIN") (class "Default")
      (node (ref "C6") (pin "2") (pinfunction "2_2") (pintype "bidirectional"))
      (node (ref "CT1") (pin "-") (pinfunction "-_-") (pintype "passive"))
      (node (ref "U$1") (pin "VIN") (pinfunction "VIN_VIN") (pintype "bidirectional"))
      (node (ref "X1") (pin "1") (pinfunction "KL_1") (pintype "passive"))
    )
    (net (code "100") (name "X1") (class "Default")
      (node (ref "C1") (pin "1") (pinfunction "1_1") (pintype "bidirectional"))
      (node (ref "U1") (pin "9") (pinfunction "X1_9") (pintype "bidirectional"))
      (node (ref "Y1") (pin "2") (pinfunction "2_2") (pintype "passive"))
    )
    (net (code "101") (name "X2") (class "Default")
      (node (ref "C2") (pin "1") (pinfunction "1_1") (pintype "bidirectional"))
      (node (ref "U1") (pin "10") (pinfunction "X2_10") (pintype "bidirectional"))
      (node (ref "Y1") (pin "1") (pinfunction "1_1") (pintype "passive"))
    )
  )
)
